# stamp_main_ESP32C3_V5_1.net
KiCad netlist of a schematic drawn in EAGLE
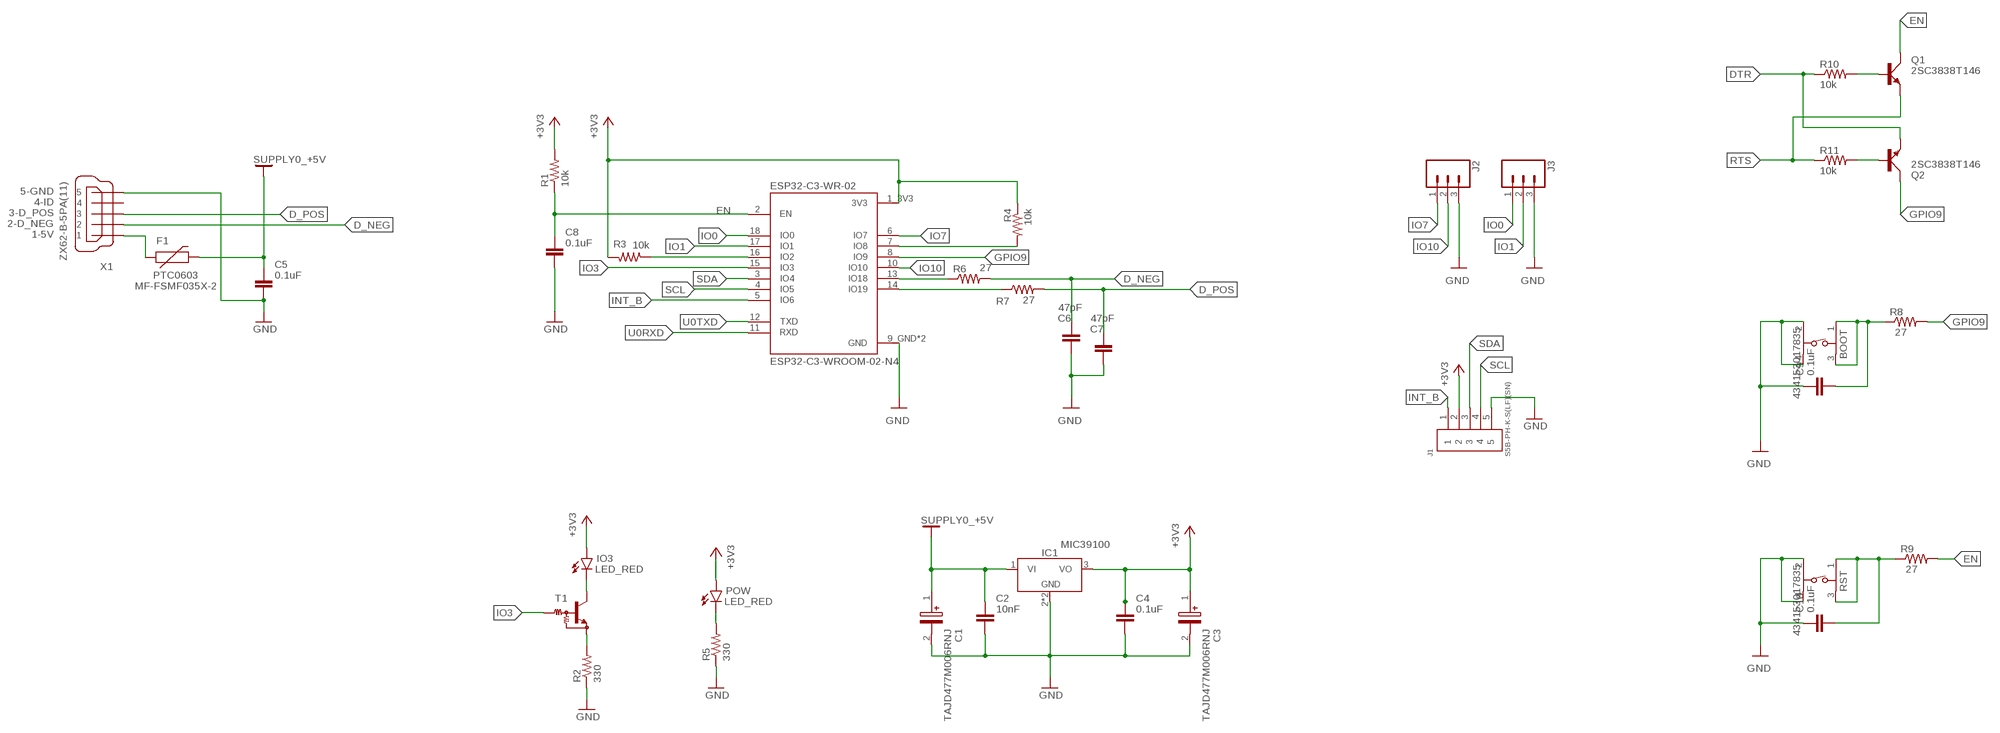
[diagram p0: schematic, sheet 1]

(export (version "E")
  (design (tool "Eeschema 10.0.6"))
  (components
    (comp (ref "BOOT")
      (value "434153017835")
      (footprint "eagle-import:434153017835")
      (libsource (lib "eagle-import") (part "434153017835"))
    )
    (comp (ref "C1")
      (value "TAJD477M006RNJ")
      (footprint "eagle-import:CAPPM7344X310N")
      (fields (field (name "MOUSER_PART_NUMBER") "581-TAJD477M006R"))
      (libsource (lib "eagle-import") (part "TAJD477M006RNJ"))
    )
    (comp (ref "C2")
      (value "10nF")
      (footprint "eagle-import:CAPC1608X85")
      (libsource (lib "eagle-import") (part "CCHIP-0603(1608-METRIC)_"))
    )
    (comp (ref "C3")
      (value "TAJD477M006RNJ")
      (footprint "eagle-import:CAPPM7344X310N")
      (fields (field (name "MOUSER_PART_NUMBER") "581-TAJD477M006R"))
      (libsource (lib "eagle-import") (part "TAJD477M006RNJ"))
    )
    (comp (ref "C4")
      (value "0.1uF")
      (footprint "eagle-import:CAPC1608X85")
      (libsource (lib "eagle-import") (part "CCHIP-0603(1608-METRIC)_"))
    )
    (comp (ref "C5")
      (value "0.1uF")
      (footprint "eagle-import:CAPC1608X85")
      (libsource (lib "eagle-import") (part "CCHIP-0603(1608-METRIC)_"))
    )
    (comp (ref "C6")
      (value "47pF")
      (footprint "eagle-import:CAPC2012X110")
      (libsource (lib "eagle-import") (part "CCHIP-0805(2012-METRIC)_"))
    )
    (comp (ref "C7")
      (value "47pF")
      (footprint "eagle-import:CAPC2012X110")
      (libsource (lib "eagle-import") (part "CCHIP-0805(2012-METRIC)_"))
    )
    (comp (ref "C8")
      (value "0.1uF")
      (footprint "eagle-import:CAPC1608X85")
      (libsource (lib "eagle-import") (part "CCHIP-0603(1608-METRIC)_"))
    )
    (comp (ref "C9")
      (value "0.1uF")
      (footprint "eagle-import:CAPC1608X85")
      (libsource (lib "eagle-import") (part "CCHIP-0603(1608-METRIC)_"))
    )
    (comp (ref "C10")
      (value "0.1uF")
      (footprint "eagle-import:CAPC1608X85")
      (libsource (lib "eagle-import") (part "CCHIP-0603(1608-METRIC)_"))
    )
    (comp (ref "ESP32-C3-WR-02")
      (value "ESP32-C3-WROOM-02-N4")
      (footprint "eagle-import:MODULE_ESP32-C3-WROOM-02-H4")
      (fields (field (name "MF") "Espressif Systems"))
      (libsource (lib "eagle-import") (part "ESP32-C3-WROOM-02-N4"))
    )
    (comp (ref "F1")
      (value "PTC0603")
      (footprint "eagle-import:0603")
      (libsource (lib "eagle-import") (part "PTC0603"))
    )
    (comp (ref "IC1")
      (value "LM7805_SOT223")
      (footprint "eagle-import:SOT230P700X170-4")
      (libsource (lib "eagle-import") (part "LM7805_SOT223"))
    )
    (comp (ref "IO3")
      (value "LED_RED")
      (footprint "eagle-import:LEDC1608X39N_R")
      (libsource (lib "eagle-import") (part "LED_CHIPRED-1608_"))
    )
    (comp (ref "J1")
      (value "S5B-PH-K-S(LF)(SN)")
      (footprint "eagle-import:S5B-PH-K-S(LF)(SN)")
      (fields
        (field (name "DIGIKEY_PARTNO") "455-1722-ND")
        (field (name "MANUFACTURER") "JST Sales America Inc.")
        (field (name "CREATED_BY") "PCBLayout.com")
      )
      (libsource (lib "eagle-import") (part "S5B-PH-K-S(LF)(SN)"))
    )
    (comp (ref "J2")
      (value "CONN_03")
      (footprint "eagle-import:1X03")
      (libsource (lib "eagle-import") (part "CONN_03"))
    )
    (comp (ref "J3")
      (value "CONN_03")
      (footprint "eagle-import:1X03")
      (libsource (lib "eagle-import") (part "CONN_03"))
    )
    (comp (ref "POW")
      (value "LED_RED")
      (footprint "eagle-import:LEDC1608X39N_R")
      (libsource (lib "eagle-import") (part "LED_CHIPRED-1608_"))
    )
    (comp (ref "Q1")
      (value "2SC3838T146")
      (footprint "eagle-import:SC59")
      (libsource (lib "eagle-import") (part "2SC3838T146"))
    )
    (comp (ref "Q2")
      (value "2SC3838T146")
      (footprint "eagle-import:SC59")
      (libsource (lib "eagle-import") (part "2SC3838T146"))
    )
    (comp (ref "R1")
      (value "10k")
      (footprint "eagle-import:R0805")
      (libsource (lib "eagle-import") (part "R-US_R0805"))
    )
    (comp (ref "R2")
      (value "330")
      (footprint "eagle-import:R0805")
      (libsource (lib "eagle-import") (part "R-US_R0805"))
    )
    (comp (ref "R3")
      (value "10k")
      (footprint "eagle-import:R0805")
      (libsource (lib "eagle-import") (part "R-US_R0805"))
    )
    (comp (ref "R4")
      (value "10k")
      (footprint "eagle-import:R0805")
      (libsource (lib "eagle-import") (part "R-US_R0805"))
    )
    (comp (ref "R5")
      (value "330")
      (footprint "eagle-import:R0805")
      (libsource (lib "eagle-import") (part "R-US_R0805"))
    )
    (comp (ref "R6")
      (value "27")
      (footprint "eagle-import:R0805")
      (libsource (lib "eagle-import") (part "R-US_R0805"))
    )
    (comp (ref "R7")
      (value "27")
      (footprint "eagle-import:R0805")
      (libsource (lib "eagle-import") (part "R-US_R0805"))
    )
    (comp (ref "R8")
      (value "27")
      (footprint "eagle-import:R0805")
      (libsource (lib "eagle-import") (part "R-US_R0805"))
    )
    (comp (ref "R9")
      (value "27")
      (footprint "eagle-import:R0805")
      (libsource (lib "eagle-import") (part "R-US_R0805"))
    )
    (comp (ref "R10")
      (value "10k")
      (footprint "eagle-import:R0805")
      (libsource (lib "eagle-import") (part "R-US_R0805"))
    )
    (comp (ref "R11")
      (value "10k")
      (footprint "eagle-import:R0805")
      (libsource (lib "eagle-import") (part "R-US_R0805"))
    )
    (comp (ref "RST")
      (value "434153017835")
      (footprint "eagle-import:434153017835")
      (libsource (lib "eagle-import") (part "434153017835"))
    )
    (comp (ref "T1")
      (value "MUN2211T1-NPN_DRIVER-SC59-BEC")
      (footprint "eagle-import:SC59-BEC")
      (libsource (lib "eagle-import") (part "-NPN_DRIVER-SC59-BECMUN2211T1"))
    )
    (comp (ref "X1")
      (value "ZX62-B-5PA(11)")
      (footprint "eagle-import:ZX62-B-5PA(11)")
      (libsource (lib "eagle-import") (part "ZX62-B-5PA(11)"))
    )
  )
  (nets
    (net (code "1") (name "+3V3") (class "Default")
      (node (ref "C3") (pin "1") (pinfunction "+_1") (pintype "bidirectional"))
      (node (ref "C4") (pin "1") (pinfunction "1_1") (pintype "passive"))
      (node (ref "ESP32-C3-WR-02") (pin "1_3V3") (pinfunction "3V3_1_3V3") (pintype "power_in"))
      (node (ref "IC1") (pin "3") (pinfunction "VO_3") (pintype "output"))
      (node (ref "IO3") (pin "2") (pinfunction "A_2") (pintype "passive"))
      (node (ref "J1") (pin "2") (pinfunction "2_2") (pintype "passive"))
      (node (ref "POW") (pin "2") (pinfunction "A_2") (pintype "passive"))
      (node (ref "R1") (pin "2") (pinfunction "2_2") (pintype "passive"))
      (node (ref "R3") (pin "2") (pinfunction "2_2") (pintype "passive"))
      (node (ref "R4") (pin "1") (pinfunction "1_1") (pintype "passive"))
    )
    (net (code "2") (name "DTR") (class "Default")
      (node (ref "Q2") (pin "E") (pinfunction "E_E") (pintype "passive"))
      (node (ref "R10") (pin "1") (pinfunction "1_1") (pintype "passive"))
    )
    (net (code "3") (name "D_NEG") (class "Default")
      (node (ref "C6") (pin "1") (pinfunction "1_1") (pintype "passive"))
      (node (ref "R6") (pin "2") (pinfunction "2_2") (pintype "passive"))
      (node (ref "X1") (pin "2") (pinfunction "2_2") (pintype "output"))
    )
    (net (code "4") (name "D_POS") (class "Default")
      (node (ref "C7") (pin "1") (pinfunction "1_1") (pintype "passive"))
      (node (ref "R7") (pin "2") (pinfunction "2_2") (pintype "passive"))
      (node (ref "X1") (pin "3") (pinfunction "3_3") (pintype "bidirectional"))
    )
    (net (code "5") (name "EN") (class "Default")
      (node (ref "C8") (pin "1") (pinfunction "1_1") (pintype "passive"))
      (node (ref "ESP32-C3-WR-02") (pin "2") (pinfunction "EN_2") (pintype "input"))
      (node (ref "Q1") (pin "C") (pinfunction "C_C") (pintype "passive"))
      (node (ref "R1") (pin "1") (pinfunction "1_1") (pintype "passive"))
      (node (ref "R9") (pin "2") (pinfunction "2_2") (pintype "passive"))
    )
    (net (code "6") (name "GND") (class "Default")
      (node (ref "BOOT") (pin "2") (pinfunction "3_2") (pintype "passive"))
      (node (ref "BOOT") (pin "4") (pinfunction "4_4") (pintype "passive"))
      (node (ref "C1") (pin "2") (pinfunction "-_2") (pintype "bidirectional"))
      (node (ref "C10") (pin "1") (pinfunction "1_1") (pintype "passive"))
      (node (ref "C2") (pin "2") (pinfunction "2_2") (pintype "passive"))
      (node (ref "C3") (pin "2") (pinfunction "-_2") (pintype "bidirectional"))
      (node (ref "C4") (pin "2") (pinfunction "2_2") (pintype "passive"))
      (node (ref "C5") (pin "2") (pinfunction "2_2") (pintype "passive"))
      (node (ref "C6") (pin "2") (pinfunction "2_2") (pintype "passive"))
      (node (ref "C7") (pin "2") (pinfunction "2_2") (pintype "passive"))
      (node (ref "C8") (pin "2") (pinfunction "2_2") (pintype "passive"))
      (node (ref "C9") (pin "1") (pinfunction "1_1") (pintype "passive"))
      (node (ref "ESP32-C3-WR-02") (pin "9_GND") (pinfunction "GND_9_GND") (pintype "power_in"))
      (node (ref "ESP32-C3-WR-02") (pin "P$1_GND") (pinfunction "GND_P$1_GND") (pintype "power_in"))
      (node (ref "IC1") (pin "2") (pinfunction "GND_2") (pintype "passive"))
      (node (ref "IC1") (pin "4") (pinfunction "GND_4") (pintype "passive"))
      (node (ref "J1") (pin "5") (pinfunction "5_5") (pintype "passive"))
      (node (ref "J2") (pin "3") (pinfunction "3_3") (pintype "passive"))
      (node (ref "J3") (pin "3") (pinfunction "3_3") (pintype "passive"))
      (node (ref "R2") (pin "1") (pinfunction "1_1") (pintype "passive"))
      (node (ref "R5") (pin "1") (pinfunction "1_1") (pintype "passive"))
      (node (ref "RST") (pin "2") (pinfunction "3_2") (pintype "passive"))
      (node (ref "RST") (pin "4") (pinfunction "4_4") (pintype "passive"))
      (node (ref "X1") (pin "5") (pinfunction "5_5") (pintype "power_in"))
    )
    (net (code "7") (name "GPIO9") (class "Default")
      (node (ref "ESP32-C3-WR-02") (pin "8") (pinfunction "IO9_8") (pintype "bidirectional"))
      (node (ref "Q2") (pin "C") (pinfunction "C_C") (pintype "passive"))
      (node (ref "R8") (pin "2") (pinfunction "2_2") (pintype "passive"))
    )
    (net (code "8") (name "INT_B") (class "Default")
      (node (ref "ESP32-C3-WR-02") (pin "5") (pinfunction "IO6_5") (pintype "bidirectional"))
      (node (ref "J1") (pin "1") (pinfunction "1_1") (pintype "passive"))
    )
    (net (code "9") (name "IO0") (class "Default")
      (node (ref "ESP32-C3-WR-02") (pin "18") (pinfunction "IO0_18") (pintype "bidirectional"))
      (node (ref "J3") (pin "1") (pinfunction "1_1") (pintype "passive"))
    )
    (net (code "10") (name "IO1") (class "Default")
      (node (ref "ESP32-C3-WR-02") (pin "17") (pinfunction "IO1_17") (pintype "bidirectional"))
      (node (ref "J3") (pin "2") (pinfunction "2_2") (pintype "passive"))
    )
    (net (code "11") (name "IO3") (class "Default")
      (node (ref "ESP32-C3-WR-02") (pin "15") (pinfunction "IO3_15") (pintype "bidirectional"))
      (node (ref "T1") (pin "B") (pinfunction "B_B") (pintype "passive"))
    )
    (net (code "12") (name "IO7") (class "Default")
      (node (ref "ESP32-C3-WR-02") (pin "6") (pinfunction "IO7_6") (pintype "bidirectional"))
      (node (ref "J2") (pin "1") (pinfunction "1_1") (pintype "passive"))
    )
    (net (code "13") (name "IO10") (class "Default")
      (node (ref "ESP32-C3-WR-02") (pin "10") (pinfunction "IO10_10") (pintype "bidirectional"))
      (node (ref "J2") (pin "2") (pinfunction "2_2") (pintype "passive"))
    )
    (net (code "14") (name "Net-(BOOT-2)") (class "Default")
      (node (ref "BOOT") (pin "1") (pinfunction "1_1") (pintype "passive"))
      (node (ref "BOOT") (pin "3") (pinfunction "2_3") (pintype "passive"))
      (node (ref "C9") (pin "2") (pinfunction "2_2") (pintype "passive"))
      (node (ref "R8") (pin "1") (pinfunction "1_1") (pintype "passive"))
    )
    (net (code "15") (name "Net-(ESP32-C3-WR-02-IO2)") (class "Default")
      (node (ref "ESP32-C3-WR-02") (pin "16") (pinfunction "IO2_16") (pintype "bidirectional"))
      (node (ref "R3") (pin "1") (pinfunction "1_1") (pintype "passive"))
    )
    (net (code "16") (name "Net-(ESP32-C3-WR-02-IO8)") (class "Default")
      (node (ref "ESP32-C3-WR-02") (pin "7") (pinfunction "IO8_7") (pintype "bidirectional"))
      (node (ref "R4") (pin "2") (pinfunction "2_2") (pintype "passive"))
    )
    (net (code "17") (name "Net-(ESP32-C3-WR-02-IO18)") (class "Default")
      (node (ref "ESP32-C3-WR-02") (pin "13") (pinfunction "IO18_13") (pintype "bidirectional"))
      (node (ref "R6") (pin "1") (pinfunction "1_1") (pintype "passive"))
    )
    (net (code "18") (name "Net-(ESP32-C3-WR-02-IO19)") (class "Default")
      (node (ref "ESP32-C3-WR-02") (pin "14") (pinfunction "IO19_14") (pintype "bidirectional"))
      (node (ref "R7") (pin "1") (pinfunction "1_1") (pintype "passive"))
    )
    (net (code "19") (name "Net-(F1-Pad1)") (class "Default")
      (node (ref "F1") (pin "1") (pinfunction "1_1") (pintype "bidirectional"))
      (node (ref "X1") (pin "1") (pinfunction "1_1") (pintype "power_in"))
    )
    (net (code "20") (name "Net-(IO3-C)") (class "Default")
      (node (ref "IO3") (pin "1") (pinfunction "C_1") (pintype "passive"))
      (node (ref "T1") (pin "C") (pinfunction "C_C") (pintype "passive"))
    )
    (net (code "21") (name "Net-(POW-C)") (class "Default")
      (node (ref "POW") (pin "1") (pinfunction "C_1") (pintype "passive"))
      (node (ref "R5") (pin "2") (pinfunction "2_2") (pintype "passive"))
    )
    (net (code "22") (name "Net-(Q1-PadB)") (class "Default")
      (node (ref "Q1") (pin "B") (pinfunction "B_B") (pintype "passive"))
      (node (ref "R10") (pin "2") (pinfunction "2_2") (pintype "passive"))
    )
    (net (code "23") (name "Net-(Q2-PadB)") (class "Default")
      (node (ref "Q2") (pin "B") (pinfunction "B_B") (pintype "passive"))
      (node (ref "R11") (pin "2") (pinfunction "2_2") (pintype "passive"))
    )
    (net (code "24") (name "Net-(R2-Pad2)") (class "Default")
      (node (ref "R2") (pin "2") (pinfunction "2_2") (pintype "passive"))
      (node (ref "T1") (pin "E") (pinfunction "E_E") (pintype "passive"))
    )
    (net (code "25") (name "Net-(RST-2)") (class "Default")
      (node (ref "C10") (pin "2") (pinfunction "2_2") (pintype "passive"))
      (node (ref "R9") (pin "1") (pinfunction "1_1") (pintype "passive"))
      (node (ref "RST") (pin "1") (pinfunction "1_1") (pintype "passive"))
      (node (ref "RST") (pin "3") (pinfunction "2_3") (pintype "passive"))
    )
    (net (code "26") (name "RTS") (class "Default")
      (node (ref "Q1") (pin "E") (pinfunction "E_E") (pintype "passive"))
      (node (ref "R11") (pin "1") (pinfunction "1_1") (pintype "passive"))
    )
    (net (code "27") (name "SCL") (class "Default")
      (node (ref "ESP32-C3-WR-02") (pin "4") (pinfunction "IO5_4") (pintype "bidirectional"))
      (node (ref "J1") (pin "4") (pinfunction "4_4") (pintype "passive"))
    )
    (net (code "28") (name "SDA") (class "Default")
      (node (ref "ESP32-C3-WR-02") (pin "3") (pinfunction "IO4_3") (pintype "bidirectional"))
      (node (ref "J1") (pin "3") (pinfunction "3_3") (pintype "passive"))
    )
    (net (code "29") (name "SUPPLY0_+5V") (class "Default")
      (node (ref "C1") (pin "1") (pinfunction "+_1") (pintype "bidirectional"))
      (node (ref "C2") (pin "1") (pinfunction "1_1") (pintype "passive"))
      (node (ref "C5") (pin "1") (pinfunction "1_1") (pintype "passive"))
      (node (ref "F1") (pin "2") (pinfunction "2_2") (pintype "bidirectional"))
      (node (ref "IC1") (pin "1") (pinfunction "VI_1") (pintype "input"))
    )
    (net (code "30") (name "U0RXD") (class "Default")
      (node (ref "ESP32-C3-WR-02") (pin "11") (pinfunction "RXD_11") (pintype "bidirectional"))
    )
    (net (code "31") (name "U0TXD") (class "Default")
      (node (ref "ESP32-C3-WR-02") (pin "12") (pinfunction "TXD_12") (pintype "bidirectional"))
    )
    (net (code "32") (name "unconnected-(X1-Pad4)") (class "Default")
      (node (ref "X1") (pin "4") (pinfunction "4_4") (pintype "passive"))
    )
  )
)
